# RF.net
KiCad netlist of a schematic drawn in Altium Designer
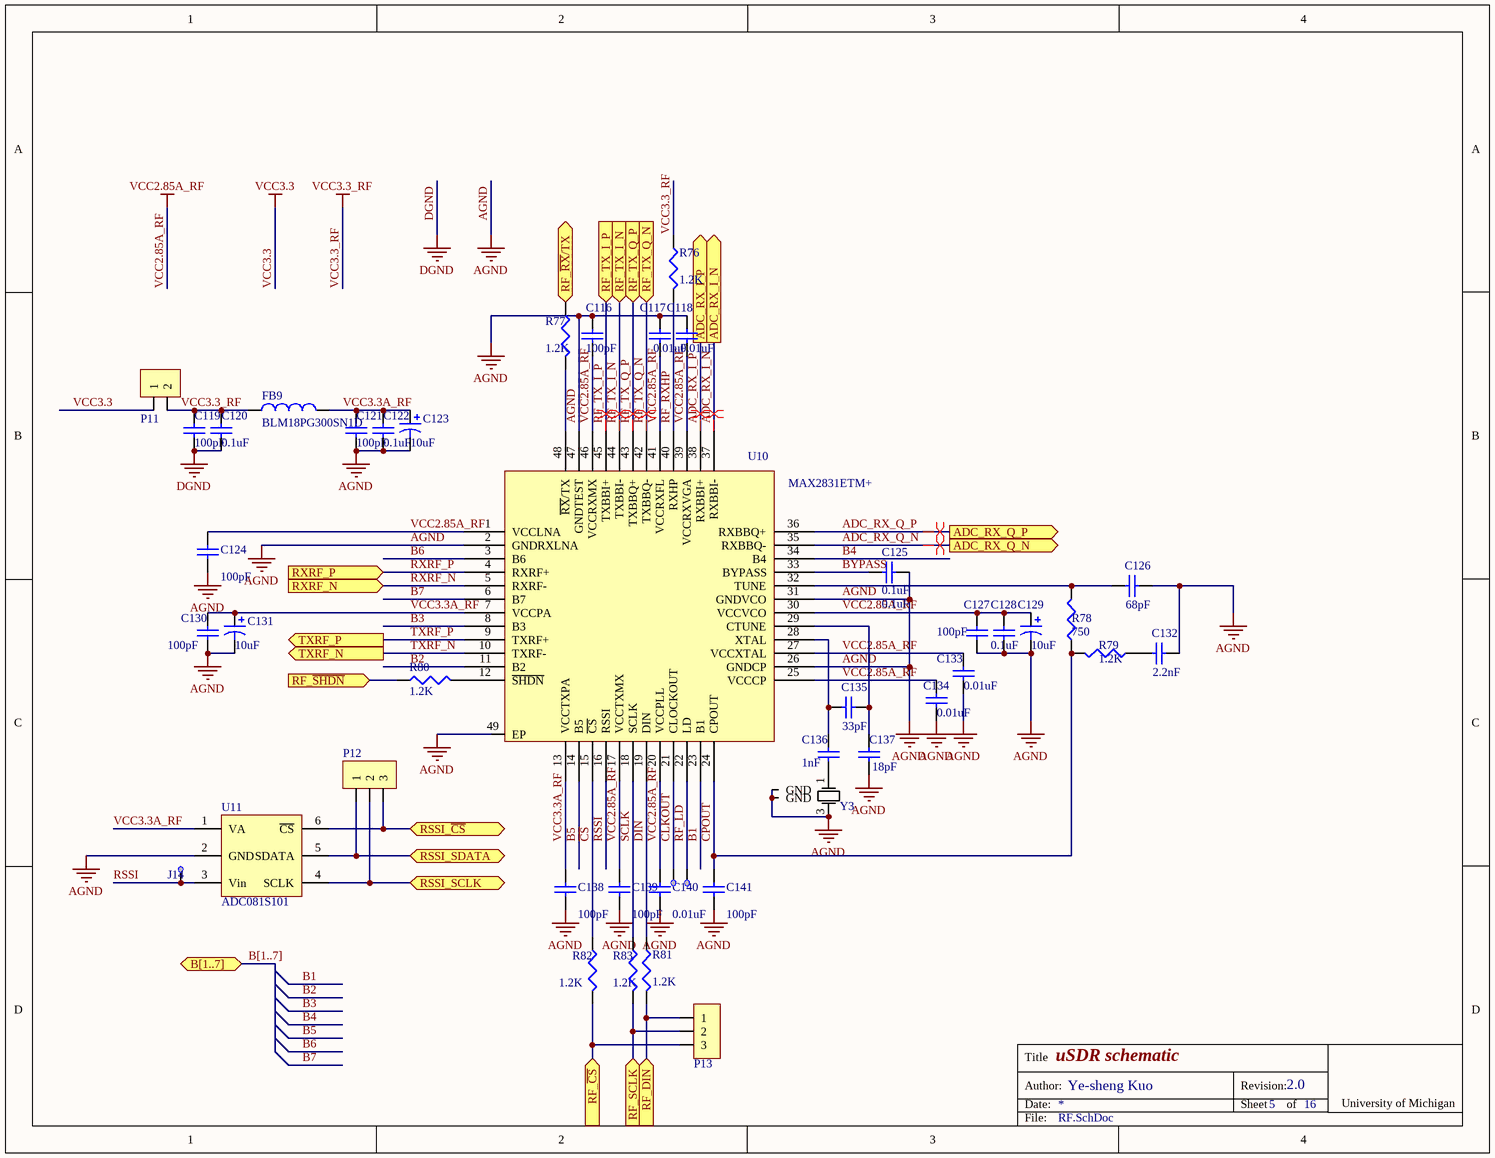
[diagram p0: RF.SchDoc]

(export (version "E")
  (design (tool "Eeschema 10.0.6"))
  (components
    (comp (ref "C116")
      (value "100pF")
      (footprint "0402")
      (description "Capacitor (Semiconductor SIM Model)")
      (fields (field (name "PUBLISHER") "Altium Limited"))
      (libsource (lib "Miscellaneous Devices") (part "Cap Semi"))
    )
    (comp (ref "C117")
      (value "0.01uF")
      (footprint "0402")
      (description "Capacitor (Semiconductor SIM Model)")
      (fields (field (name "PUBLISHER") "Altium Limited"))
      (libsource (lib "Miscellaneous Devices") (part "Cap Semi"))
    )
    (comp (ref "C118")
      (value "0.01uF")
      (footprint "0402")
      (description "Capacitor (Semiconductor SIM Model)")
      (fields (field (name "PUBLISHER") "Altium Limited"))
      (libsource (lib "Miscellaneous Devices") (part "Cap Semi"))
    )
    (comp (ref "C119")
      (value "100pF")
      (footprint "0402")
      (description "Capacitor (Semiconductor SIM Model)")
      (fields (field (name "PUBLISHER") "Altium Limited"))
      (libsource (lib "Miscellaneous Devices") (part "Cap Semi"))
    )
    (comp (ref "C120")
      (value "0.1uF")
      (footprint "0402")
      (description "Capacitor (Semiconductor SIM Model)")
      (fields (field (name "PUBLISHER") "Altium Limited"))
      (libsource (lib "Miscellaneous Devices") (part "Cap Semi"))
    )
    (comp (ref "C121")
      (value "100pF")
      (footprint "0402")
      (description "Capacitor (Semiconductor SIM Model)")
      (fields (field (name "PUBLISHER") "Altium Limited"))
      (libsource (lib "Miscellaneous Devices") (part "Cap Semi"))
    )
    (comp (ref "C122")
      (value "0.1uF")
      (footprint "0402")
      (description "Capacitor (Semiconductor SIM Model)")
      (fields (field (name "PUBLISHER") "Altium Limited"))
      (libsource (lib "Miscellaneous Devices") (part "Cap Semi"))
    )
    (comp (ref "C123")
      (value "10uF")
      (footprint "C0805")
      (description "Polarized Capacitor (Surface Mount)")
      (fields (field (name "PUBLISHER") "Altium Limited"))
      (libsource (lib "Miscellaneous Devices") (part "Cap Pol3"))
    )
    (comp (ref "C124")
      (value "100pF")
      (footprint "0402")
      (description "Capacitor (Semiconductor SIM Model)")
      (fields (field (name "PUBLISHER") "Altium Limited"))
      (libsource (lib "Miscellaneous Devices") (part "Cap Semi"))
    )
    (comp (ref "C125")
      (value "0.1uF")
      (footprint "0402")
      (description "Capacitor (Semiconductor SIM Model)")
      (fields (field (name "ALTIUM_VALUE") "0.1uF") (field (name "PUBLISHER") "Altium Limited"))
      (libsource (lib "Miscellaneous Devices") (part "Cap Semi"))
    )
    (comp (ref "C126")
      (value "68pF")
      (footprint "0402")
      (description "Capacitor (Semiconductor SIM Model)")
      (fields (field (name "PUBLISHER") "Altium Limited"))
      (libsource (lib "Miscellaneous Devices") (part "Cap Semi"))
    )
    (comp (ref "C127")
      (value "100pF")
      (footprint "0402")
      (description "Capacitor (Semiconductor SIM Model)")
      (fields (field (name "PUBLISHER") "Altium Limited"))
      (libsource (lib "Miscellaneous Devices") (part "Cap Semi"))
    )
    (comp (ref "C128")
      (value "0.1uF")
      (footprint "0402")
      (description "Capacitor (Semiconductor SIM Model)")
      (fields (field (name "PUBLISHER") "Altium Limited"))
      (libsource (lib "Miscellaneous Devices") (part "Cap Semi"))
    )
    (comp (ref "C129")
      (value "10uF")
      (footprint "C0805")
      (description "Polarized Capacitor (Surface Mount)")
      (fields (field (name "PUBLISHER") "Altium Limited"))
      (libsource (lib "Miscellaneous Devices") (part "Cap Pol3"))
    )
    (comp (ref "C130")
      (value "100pF")
      (footprint "0402")
      (description "Capacitor (Semiconductor SIM Model)")
      (fields (field (name "PUBLISHER") "Altium Limited"))
      (libsource (lib "Miscellaneous Devices") (part "Cap Semi"))
    )
    (comp (ref "C131")
      (value "10uF")
      (footprint "C0805")
      (description "Polarized Capacitor (Surface Mount)")
      (fields (field (name "PUBLISHER") "Altium Limited"))
      (libsource (lib "Miscellaneous Devices") (part "Cap Pol3"))
    )
    (comp (ref "C132")
      (value "2.2nF")
      (footprint "0402")
      (description "Capacitor (Semiconductor SIM Model)")
      (fields (field (name "PUBLISHER") "Altium Limited"))
      (libsource (lib "Miscellaneous Devices") (part "Cap Semi"))
    )
    (comp (ref "C133")
      (value "0.01uF")
      (footprint "0402")
      (description "Capacitor (Semiconductor SIM Model)")
      (fields (field (name "PUBLISHER") "Altium Limited"))
      (libsource (lib "Miscellaneous Devices") (part "Cap Semi"))
    )
    (comp (ref "C134")
      (value "0.01uF")
      (footprint "0402")
      (description "Capacitor (Semiconductor SIM Model)")
      (fields (field (name "PUBLISHER") "Altium Limited"))
      (libsource (lib "Miscellaneous Devices") (part "Cap Semi"))
    )
    (comp (ref "C135")
      (value "33pF")
      (footprint "0402")
      (description "Capacitor (Semiconductor SIM Model)")
      (fields (field (name "PUBLISHER") "Altium Limited"))
      (libsource (lib "Miscellaneous Devices") (part "Cap Semi"))
    )
    (comp (ref "C136")
      (value "1nF")
      (footprint "0402")
      (description "Capacitor (Semiconductor SIM Model)")
      (fields (field (name "PUBLISHER") "Altium Limited"))
      (libsource (lib "Miscellaneous Devices") (part "Cap Semi"))
    )
    (comp (ref "C137")
      (value "18pF")
      (footprint "0402")
      (description "Capacitor (Semiconductor SIM Model)")
      (fields (field (name "PUBLISHER") "Altium Limited"))
      (libsource (lib "Miscellaneous Devices") (part "Cap Semi"))
    )
    (comp (ref "C138")
      (value "100pF")
      (footprint "0402")
      (description "Capacitor (Semiconductor SIM Model)")
      (fields (field (name "PUBLISHER") "Altium Limited"))
      (libsource (lib "Miscellaneous Devices") (part "Cap Semi"))
    )
    (comp (ref "C139")
      (value "100pF")
      (footprint "0402")
      (description "Capacitor (Semiconductor SIM Model)")
      (fields (field (name "PUBLISHER") "Altium Limited"))
      (libsource (lib "Miscellaneous Devices") (part "Cap Semi"))
    )
    (comp (ref "C140")
      (value "0.01uF")
      (footprint "0402")
      (description "Capacitor (Semiconductor SIM Model)")
      (fields (field (name "PUBLISHER") "Altium Limited"))
      (libsource (lib "Miscellaneous Devices") (part "Cap Semi"))
    )
    (comp (ref "C141")
      (value "100pF")
      (footprint "0402")
      (description "Capacitor (Semiconductor SIM Model)")
      (fields (field (name "PUBLISHER") "Altium Limited"))
      (libsource (lib "Miscellaneous Devices") (part "Cap Semi"))
    )
    (comp (ref "FB9")
      (value "BLM18PG300SN1D")
      (footprint "1608[0603]")
      (description "FERRITE CHIP 30 OHM 1000MA 0603")
      (libsource (lib "SDR") (part "Ferrite Bead"))
    )
    (comp (ref "J14")
      (value "5004")
      (footprint "TestPoint")
      (description "TEST POINT PC MINI .040\"D YELLOW")
      (libsource (lib "SDR") (part "TestPoint"))
    )
    (comp (ref "J15")
      (value "5004")
      (footprint "TestPoint")
      (description "TEST POINT PC MINI .040\"D YELLOW")
      (libsource (lib "SDR") (part "TestPoint"))
    )
    (comp (ref "J16")
      (value "5004")
      (footprint "TestPoint")
      (description "TEST POINT PC MINI .040\"D YELLOW")
      (libsource (lib "SDR") (part "TestPoint"))
    )
    (comp (ref "P11")
      (value "1 x 2 header")
      (footprint "1x2 header")
      (description "100 mils standard header")
      (libsource (lib "SDR") (part "1 x 2 header"))
    )
    (comp (ref "P12")
      (value "1 x 3 header")
      (footprint "1x3 header")
      (description "100 mils standard header")
      (libsource (lib "SDR") (part "1 x 3 header"))
    )
    (comp (ref "P13")
      (value "1 x 3 header")
      (footprint "1x3 header")
      (description "100 mils standard header")
      (libsource (lib "") (part "1 x 3 header_1"))
    )
    (comp (ref "R76")
      (value "1.2K")
      (footprint "0402")
      (description "Resistor")
      (fields (field (name "PUBLISHER") "Altium Limited"))
      (libsource (lib "Miscellaneous Devices") (part "Res3"))
    )
    (comp (ref "R77")
      (value "1.2K")
      (footprint "0402")
      (description "Resistor")
      (fields (field (name "PUBLISHER") "Altium Limited"))
      (libsource (lib "Miscellaneous Devices") (part "Res3"))
    )
    (comp (ref "R78")
      (value "750")
      (footprint "0402")
      (description "Resistor")
      (fields (field (name "PUBLISHER") "Altium Limited"))
      (libsource (lib "Miscellaneous Devices") (part "Res3"))
    )
    (comp (ref "R79")
      (value "1.2K")
      (footprint "0402")
      (description "Resistor")
      (fields (field (name "PUBLISHER") "Altium Limited"))
      (libsource (lib "Miscellaneous Devices") (part "Res3"))
    )
    (comp (ref "R80")
      (value "1.2K")
      (footprint "0402")
      (description "Resistor")
      (fields (field (name "PUBLISHER") "Altium Limited"))
      (libsource (lib "Miscellaneous Devices") (part "Res3"))
    )
    (comp (ref "R81")
      (value "1.2K")
      (footprint "0402")
      (description "Resistor")
      (fields (field (name "PUBLISHER") "Altium Limited"))
      (libsource (lib "Miscellaneous Devices") (part "Res3"))
    )
    (comp (ref "R82")
      (value "1.2K")
      (footprint "0402")
      (description "Resistor")
      (fields (field (name "PUBLISHER") "Altium Limited"))
      (libsource (lib "Miscellaneous Devices") (part "Res3"))
    )
    (comp (ref "R83")
      (value "1.2K")
      (footprint "0402")
      (description "Resistor")
      (fields (field (name "PUBLISHER") "Altium Limited"))
      (libsource (lib "Miscellaneous Devices") (part "Res3"))
    )
    (comp (ref "U10")
      (value "MAX2831ETM+")
      (footprint "TQFN-48")
      (description "RF Transceiver 2.4-2.5GHz 802.11g/b RF Transceiver")
      (libsource (lib "SDR") (part "MAX2831"))
    )
    (comp (ref "U11")
      (value "ADC081S101")
      (footprint "SOT23-6")
      (description "IC ADC 8BIT 1MSPS SOT23-6")
      (libsource (lib "SDR") (part "ADC081S101"))
    )
    (comp (ref "Y3")
      (value "CX2520SB40000H0DZF08")
      (footprint "CX-2520SB")
      (description "CRYSTAL 40.000MHZ 12PF SMD")
      (libsource (lib "SDR") (part "CX-2520SB"))
    )
  )
  (nets
    (net (code "1") (name "/ADC_RX_I_N") (class "Default")
      (node (ref "U10") (pin "37") (pinfunction "RXBBI-_37") (pintype "passive"))
    )
    (net (code "2") (name "/ADC_RX_I_P") (class "Default")
      (node (ref "U10") (pin "38") (pinfunction "RXBBI+_38") (pintype "passive"))
    )
    (net (code "3") (name "/ADC_RX_Q_N") (class "Default")
      (node (ref "U10") (pin "35") (pinfunction "RXBBQ-_35") (pintype "passive"))
    )
    (net (code "4") (name "/ADC_RX_Q_P") (class "Default")
      (node (ref "U10") (pin "36") (pinfunction "RXBBQ+_36") (pintype "passive"))
    )
    (net (code "5") (name "/B1") (class "Default")
      (node (ref "U10") (pin "23") (pinfunction "B1_23") (pintype "passive"))
    )
    (net (code "6") (name "/B2") (class "Default")
      (node (ref "U10") (pin "11") (pinfunction "B2_11") (pintype "passive"))
    )
    (net (code "7") (name "/B3") (class "Default")
      (node (ref "U10") (pin "8") (pinfunction "B3_8") (pintype "passive"))
    )
    (net (code "8") (name "/B4") (class "Default")
      (node (ref "U10") (pin "34") (pinfunction "B4_34") (pintype "passive"))
    )
    (net (code "9") (name "/B5") (class "Default")
      (node (ref "U10") (pin "14") (pinfunction "B5_14") (pintype "passive"))
    )
    (net (code "10") (name "/B6") (class "Default")
      (node (ref "U10") (pin "3") (pinfunction "B6_3") (pintype "passive"))
    )
    (net (code "11") (name "/B7") (class "Default")
      (node (ref "U10") (pin "6") (pinfunction "B7_6") (pintype "passive"))
    )
    (net (code "12") (name "/BYPASS") (class "Default")
      (node (ref "C125") (pin "1") (pinfunction "1_1") (pintype "passive"))
      (node (ref "U10") (pin "33") (pinfunction "BYPASS_33") (pintype "passive"))
    )
    (net (code "14") (name "/CLKOUT") (class "Default")
      (node (ref "J15") (pin "1") (pinfunction "TB_1") (pintype "passive"))
      (node (ref "U10") (pin "21") (pinfunction "CLOCKOUT_21") (pintype "passive"))
    )
    (net (code "15") (name "/CPOUT") (class "Default")
      (node (ref "C141") (pin "2") (pinfunction "2_2") (pintype "passive"))
      (node (ref "R78") (pin "1") (pinfunction "1_1") (pintype "passive"))
      (node (ref "R79") (pin "2") (pinfunction "2_2") (pintype "passive"))
      (node (ref "U10") (pin "24") (pinfunction "CPOUT_24") (pintype "passive"))
    )
    (net (code "16") (name "/DIN") (class "Default")
      (node (ref "R81") (pin "1") (pinfunction "1_1") (pintype "passive"))
      (node (ref "U10") (pin "19") (pinfunction "DIN_19") (pintype "passive"))
    )
    (net (code "17") (name "/RF_DIN") (class "Default")
      (node (ref "P13") (pin "1") (pinfunction "1_1") (pintype "passive"))
      (node (ref "R81") (pin "2") (pinfunction "2_2") (pintype "passive"))
    )
    (net (code "18") (name "/RF_LD") (class "Default")
      (node (ref "J16") (pin "1") (pinfunction "TB_1") (pintype "passive"))
      (node (ref "U10") (pin "22") (pinfunction "LD_22") (pintype "passive"))
    )
    (net (code "19") (name "/RF_RXHP") (class "Default")
      (node (ref "R76") (pin "2") (pinfunction "2_2") (pintype "passive"))
      (node (ref "U10") (pin "40") (pinfunction "RXHP_40") (pintype "passive"))
    )
    (net (code "20") (name "/RF_SCLK") (class "Default")
      (node (ref "P13") (pin "2") (pinfunction "2_2") (pintype "passive"))
      (node (ref "R83") (pin "2") (pinfunction "2_2") (pintype "passive"))
    )
    (net (code "21") (name "/RF_TX_I_N") (class "Default")
      (node (ref "U10") (pin "44") (pinfunction "TXBBI-_44") (pintype "passive"))
    )
    (net (code "22") (name "/RF_TX_I_P") (class "Default")
      (node (ref "U10") (pin "45") (pinfunction "TXBBI+_45") (pintype "passive"))
    )
    (net (code "23") (name "/RF_TX_Q_N") (class "Default")
      (node (ref "U10") (pin "42") (pinfunction "TXBBQ-_42") (pintype "passive"))
    )
    (net (code "24") (name "/RF_TX_Q_P") (class "Default")
      (node (ref "U10") (pin "43") (pinfunction "TXBBQ+_43") (pintype "passive"))
    )
    (net (code "25") (name "/RF_~{CS}") (class "Default")
      (node (ref "P13") (pin "3") (pinfunction "3_3") (pintype "passive"))
      (node (ref "R82") (pin "2") (pinfunction "2_2") (pintype "passive"))
    )
    (net (code "26") (name "/RF_~{RX}{slash}TX") (class "Default")
      (node (ref "R77") (pin "1") (pinfunction "1_1") (pintype "passive"))
    )
    (net (code "27") (name "/RF_~{SHDN}") (class "Default")
      (node (ref "R80") (pin "1") (pinfunction "1_1") (pintype "passive"))
    )
    (net (code "28") (name "/RSSI") (class "Default")
      (node (ref "J14") (pin "1") (pinfunction "TB_1") (pintype "passive"))
      (node (ref "U10") (pin "16") (pinfunction "RSSI_16") (pintype "passive"))
      (node (ref "U11") (pin "3") (pinfunction "Vin_3") (pintype "passive"))
    )
    (net (code "29") (name "/RSSI_SCLK") (class "Default")
      (node (ref "P12") (pin "2") (pinfunction "2_2") (pintype "passive"))
      (node (ref "U11") (pin "4") (pinfunction "SCLK_4") (pintype "passive"))
    )
    (net (code "30") (name "/RSSI_SDATA") (class "Default")
      (node (ref "P12") (pin "1") (pinfunction "1_1") (pintype "passive"))
      (node (ref "U11") (pin "5") (pinfunction "SDATA_5") (pintype "passive"))
    )
    (net (code "31") (name "/RSSI_~{CS}") (class "Default")
      (node (ref "P12") (pin "3") (pinfunction "3_3") (pintype "passive"))
      (node (ref "U11") (pin "6") (pinfunction "~{CS}_6") (pintype "passive"))
    )
    (net (code "32") (name "/RXRF_N") (class "Default")
      (node (ref "U10") (pin "5") (pinfunction "RXRF-_5") (pintype "passive"))
    )
    (net (code "33") (name "/RXRF_P") (class "Default")
      (node (ref "U10") (pin "4") (pinfunction "RXRF+_4") (pintype "passive"))
    )
    (net (code "34") (name "/SCLK") (class "Default")
      (node (ref "R83") (pin "1") (pinfunction "1_1") (pintype "passive"))
      (node (ref "U10") (pin "18") (pinfunction "SCLK_18") (pintype "passive"))
    )
    (net (code "35") (name "/TXRF_N") (class "Default")
      (node (ref "U10") (pin "10") (pinfunction "TXRF-_10") (pintype "passive"))
    )
    (net (code "36") (name "/TXRF_P") (class "Default")
      (node (ref "U10") (pin "9") (pinfunction "TXRF+_9") (pintype "passive"))
    )
    (net (code "37") (name "/VCC3.3A_RF") (class "Default")
      (node (ref "C121") (pin "2") (pinfunction "2_2") (pintype "passive"))
      (node (ref "C122") (pin "2") (pinfunction "2_2") (pintype "passive"))
      (node (ref "C123") (pin "1") (pinfunction "1_1") (pintype "passive"))
      (node (ref "C130") (pin "2") (pinfunction "2_2") (pintype "passive"))
      (node (ref "C131") (pin "1") (pinfunction "1_1") (pintype "passive"))
      (node (ref "C138") (pin "2") (pinfunction "2_2") (pintype "passive"))
      (node (ref "FB9") (pin "2") (pinfunction "2_2") (pintype "passive"))
      (node (ref "U10") (pin "13") (pinfunction "VCCTXPA_13") (pintype "passive"))
      (node (ref "U10") (pin "7") (pinfunction "VCCPA_7") (pintype "passive"))
      (node (ref "U11") (pin "1") (pinfunction "VA_1") (pintype "passive"))
    )
    (net (code "38") (name "/~{CS}") (class "Default")
      (node (ref "R82") (pin "1") (pinfunction "1_1") (pintype "passive"))
      (node (ref "U10") (pin "15") (pinfunction "~{CS}_15") (pintype "passive"))
    )
    (net (code "39") (name "AGND") (class "Default")
      (node (ref "C116") (pin "2") (pinfunction "2_2") (pintype "passive"))
      (node (ref "C117") (pin "2") (pinfunction "2_2") (pintype "passive"))
      (node (ref "C118") (pin "2") (pinfunction "2_2") (pintype "passive"))
      (node (ref "C121") (pin "1") (pinfunction "1_1") (pintype "passive"))
      (node (ref "C122") (pin "1") (pinfunction "1_1") (pintype "passive"))
      (node (ref "C123") (pin "2") (pinfunction "2_2") (pintype "passive"))
      (node (ref "C124") (pin "1") (pinfunction "1_1") (pintype "passive"))
      (node (ref "C125") (pin "2") (pinfunction "2_2") (pintype "passive"))
      (node (ref "C126") (pin "2") (pinfunction "2_2") (pintype "passive"))
      (node (ref "C127") (pin "1") (pinfunction "1_1") (pintype "passive"))
      (node (ref "C128") (pin "1") (pinfunction "1_1") (pintype "passive"))
      (node (ref "C129") (pin "2") (pinfunction "2_2") (pintype "passive"))
      (node (ref "C130") (pin "1") (pinfunction "1_1") (pintype "passive"))
      (node (ref "C131") (pin "2") (pinfunction "2_2") (pintype "passive"))
      (node (ref "C132") (pin "2") (pinfunction "2_2") (pintype "passive"))
      (node (ref "C133") (pin "1") (pinfunction "1_1") (pintype "passive"))
      (node (ref "C134") (pin "1") (pinfunction "1_1") (pintype "passive"))
      (node (ref "C137") (pin "1") (pinfunction "1_1") (pintype "passive"))
      (node (ref "C138") (pin "1") (pinfunction "1_1") (pintype "passive"))
      (node (ref "C139") (pin "1") (pinfunction "1_1") (pintype "passive"))
      (node (ref "C140") (pin "1") (pinfunction "1_1") (pintype "passive"))
      (node (ref "C141") (pin "1") (pinfunction "1_1") (pintype "passive"))
      (node (ref "U10") (pin "2") (pinfunction "GNDRXLNA_2") (pintype "passive"))
      (node (ref "U10") (pin "26") (pinfunction "GNDCP_26") (pintype "passive"))
      (node (ref "U10") (pin "31") (pinfunction "GNDVCO_31") (pintype "passive"))
      (node (ref "U10") (pin "47") (pinfunction "GNDTEST_47") (pintype "passive"))
      (node (ref "U10") (pin "49") (pinfunction "EP_49") (pintype "passive"))
      (node (ref "U11") (pin "2") (pinfunction "GND_2") (pintype "passive"))
      (node (ref "Y3") (pin "2") (pinfunction "GND_2") (pintype "passive"))
      (node (ref "Y3") (pin "3") (pinfunction "HOT_3") (pintype "passive"))
      (node (ref "Y3") (pin "4") (pinfunction "GND_4") (pintype "passive"))
    )
    (net (code "40") (name "DGND") (class "Default")
      (node (ref "C119") (pin "1") (pinfunction "1_1") (pintype "passive"))
      (node (ref "C120") (pin "1") (pinfunction "1_1") (pintype "passive"))
    )
    (net (code "41") (name "Net-(C132-Pad1)") (class "Default")
      (node (ref "C132") (pin "1") (pinfunction "1_1") (pintype "passive"))
      (node (ref "R79") (pin "1") (pinfunction "1_1") (pintype "passive"))
    )
    (net (code "42") (name "Net-(C136-Pad1)") (class "Default")
      (node (ref "C136") (pin "1") (pinfunction "1_1") (pintype "passive"))
      (node (ref "Y3") (pin "1") (pinfunction "HOT_1") (pintype "passive"))
    )
    (net (code "43") (name "Net-(U10-CTUNE)") (class "Default")
      (node (ref "C135") (pin "2") (pinfunction "2_2") (pintype "passive"))
      (node (ref "C137") (pin "2") (pinfunction "2_2") (pintype "passive"))
      (node (ref "U10") (pin "29") (pinfunction "CTUNE_29") (pintype "passive"))
    )
    (net (code "44") (name "Net-(U10-TUNE)") (class "Default")
      (node (ref "C126") (pin "1") (pinfunction "1_1") (pintype "passive"))
      (node (ref "R78") (pin "2") (pinfunction "2_2") (pintype "passive"))
      (node (ref "U10") (pin "32") (pinfunction "TUNE_32") (pintype "passive"))
    )
    (net (code "45") (name "Net-(U10-XTAL)") (class "Default")
      (node (ref "C135") (pin "1") (pinfunction "1_1") (pintype "passive"))
      (node (ref "C136") (pin "2") (pinfunction "2_2") (pintype "passive"))
      (node (ref "U10") (pin "28") (pinfunction "XTAL_28") (pintype "passive"))
    )
    (net (code "46") (name "Net-(U10-~{RX}{slash}TX)") (class "Default")
      (node (ref "R77") (pin "2") (pinfunction "2_2") (pintype "passive"))
      (node (ref "U10") (pin "48") (pinfunction "~{RX}/TX_48") (pintype "passive"))
    )
    (net (code "47") (name "Net-(U10-~{SHDN})") (class "Default")
      (node (ref "R80") (pin "2") (pinfunction "2_2") (pintype "passive"))
      (node (ref "U10") (pin "12") (pinfunction "~{SHDN}_12") (pintype "passive"))
    )
    (net (code "48") (name "VCC2.85A_RF") (class "Default")
      (node (ref "C116") (pin "1") (pinfunction "1_1") (pintype "passive"))
      (node (ref "C117") (pin "1") (pinfunction "1_1") (pintype "passive"))
      (node (ref "C118") (pin "1") (pinfunction "1_1") (pintype "passive"))
      (node (ref "C124") (pin "2") (pinfunction "2_2") (pintype "passive"))
      (node (ref "C127") (pin "2") (pinfunction "2_2") (pintype "passive"))
      (node (ref "C128") (pin "2") (pinfunction "2_2") (pintype "passive"))
      (node (ref "C129") (pin "1") (pinfunction "1_1") (pintype "passive"))
      (node (ref "C133") (pin "2") (pinfunction "2_2") (pintype "passive"))
      (node (ref "C134") (pin "2") (pinfunction "2_2") (pintype "passive"))
      (node (ref "C139") (pin "2") (pinfunction "2_2") (pintype "passive"))
      (node (ref "C140") (pin "2") (pinfunction "2_2") (pintype "passive"))
      (node (ref "U10") (pin "1") (pinfunction "VCCLNA_1") (pintype "passive"))
      (node (ref "U10") (pin "17") (pinfunction "VCCTXMX_17") (pintype "passive"))
      (node (ref "U10") (pin "20") (pinfunction "VCCPLL_20") (pintype "passive"))
      (node (ref "U10") (pin "25") (pinfunction "VCCCP_25") (pintype "passive"))
      (node (ref "U10") (pin "27") (pinfunction "VCCXTAL_27") (pintype "passive"))
      (node (ref "U10") (pin "30") (pinfunction "VCCVCO_30") (pintype "passive"))
      (node (ref "U10") (pin "39") (pinfunction "VCCRXVGA_39") (pintype "passive"))
      (node (ref "U10") (pin "41") (pinfunction "VCCRXFL_41") (pintype "passive"))
      (node (ref "U10") (pin "46") (pinfunction "VCCRXMX_46") (pintype "passive"))
    )
    (net (code "49") (name "VCC3.3") (class "Default")
      (node (ref "P11") (pin "1") (pinfunction "1_1") (pintype "passive"))
    )
    (net (code "50") (name "VCC3.3_RF") (class "Default")
      (node (ref "C119") (pin "2") (pinfunction "2_2") (pintype "passive"))
      (node (ref "C120") (pin "2") (pinfunction "2_2") (pintype "passive"))
      (node (ref "FB9") (pin "1") (pinfunction "1_1") (pintype "passive"))
      (node (ref "P11") (pin "2") (pinfunction "2_2") (pintype "passive"))
      (node (ref "R76") (pin "1") (pinfunction "1_1") (pintype "passive"))
    )
  )
)
